# UCC27511_MSFTDRIVER.net
KiCad netlist of a schematic drawn in Altium Designer
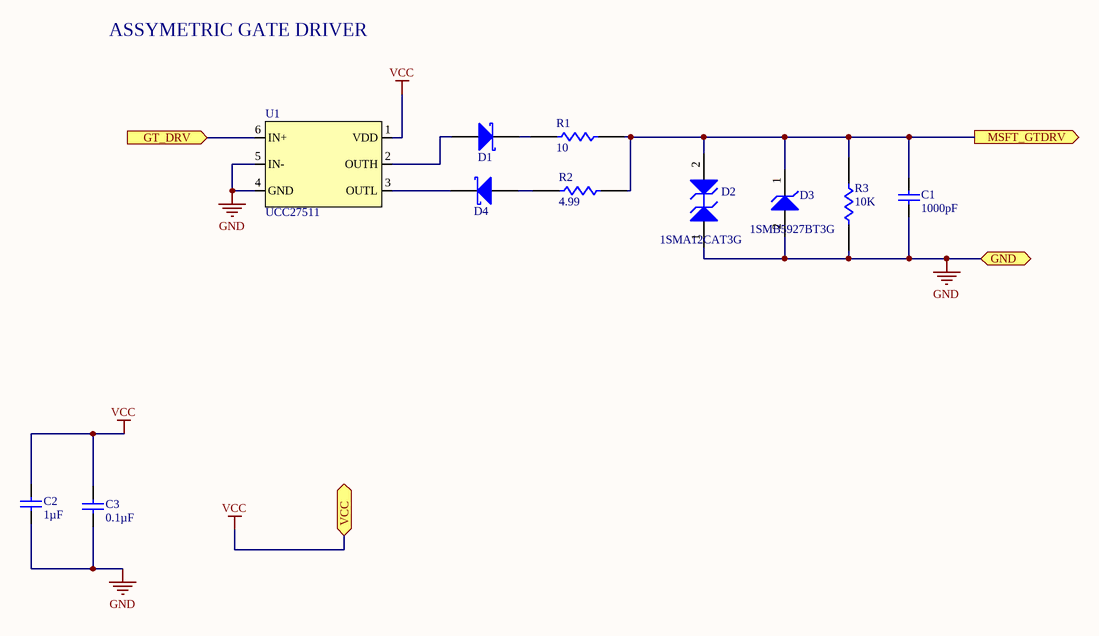
[diagram p0: UCC27511_MSFTDRIVER.SchDoc]

(export (version "E")
  (design (tool "Eeschema 10.0.6"))
  (components
    (comp (ref "C1")
      (value "C0805C102J5GACTU")
      (footprint "CAP0805_NEW")
      (description "CAP CER 1000PF 50V C0G/NP0 0805")
      (fields
        (field (name "MANUFACTURER") "KEMET")
        (field (name "TOLERANCE") "±5%")
        (field (name "CAPACITANCE") "1000pF")
      )
      (libsource (lib "ucc28180-V04") (part "C0805C102J5GACTU"))
    )
    (comp (ref "C2")
      (value "CC0805JKX7R9BB105")
      (footprint "CAP0805_NEW")
      (description "CAP CER 1UF 50V X7R 0805")
      (fields
        (field (name "MANUFACTURER") "Yageo")
        (field (name "TOLERANCE") "±5%")
        (field (name "CAPACITANCE") "1µF")
      )
      (libsource (lib "ucc28180-V04") (part "CC0805JKX7R9BB105"))
    )
    (comp (ref "C3")
      (value "C0805C104J5RACAUTO")
      (footprint "CAP0805_NEW")
      (description "CAP CER 0.1UF 50V X7R 0805")
      (fields
        (field (name "MANUFACTURER") "KEMET")
        (field (name "TOLERANCE") "±5%")
        (field (name "CAPACITANCE") "0.1µF")
      )
      (libsource (lib "ucc28180-V04") (part "C0805C104J5RACAUTO"))
    )
    (comp (ref "D1")
      (value "DB2W40300L")
      (footprint "Mini2-F3-B")
      (fields (field (name "MANUFACTURER") "Panasonic"))
      (libsource (lib "ucc28180") (part "DB2W40300L"))
    )
    (comp (ref "D2")
      (value "1SMA12CAT3G")
      (footprint "ONSC-SMA-2-403D-02_F_V")
      (description "400 W Peak Power Zener Transient Voltage Suppressor, 2-Pin SMA, Pb-Free, Tape and Reel")
      (fields (field (name "MANUFACTURER") "On Semiconductor"))
      (libsource (lib "ON Semi Transient Voltage Suppressors (TVS)") (part "1SMA12CAT3G"))
    )
    (comp (ref "D3")
      (value "1SMB5927BT3G")
      (footprint "ONSC-SMB-2-403A-03_H_V")
      (description "3 W Zener Voltage Regulator, 2-Pin SMB, Pb-Free, Tape and Reel")
      (fields (field (name "MANUFACTURER") "On Semiconductor"))
      (libsource (lib "ON Semi Zener Diodes") (part "1SMB5927BT3G"))
    )
    (comp (ref "D4")
      (value "DB2W40300L")
      (footprint "Mini2-F3-B")
      (fields (field (name "MANUFACTURER") "Panasonic"))
      (libsource (lib "ucc28180") (part "DB2W40300L"))
    )
    (comp (ref "R1")
      (value "CRCW0805R10")
      (footprint "RES0805")
      (fields (field (name "RESISTANCE") "10"))
      (libsource (lib "ucc28180") (part "CRCW0805R10"))
    )
    (comp (ref "R2")
      (value "CRCW0805R4.99")
      (footprint "RES0805")
      (fields (field (name "RESISTANCE") "4.99"))
      (libsource (lib "ucc28180") (part "CRCW0805R4.99"))
    )
    (comp (ref "R3")
      (value "TNPW080510K0FEEA")
      (footprint "RES0805_New")
      (description "RES 10K OHM 1% 1/5W 0805")
      (fields
        (field (name "MANUFACTURER") "Vishay Dale")
        (field (name "TOLERANCE") "±1%")
        (field (name "RESISTANCE") "10K")
      )
      (libsource (lib "ucc28180-V04") (part "TNPW080510K0FEEA"))
    )
    (comp (ref "U1")
      (value "UCC27511DBV")
      (footprint "SOP6")
      (fields (field (name "IC NAME") "UCC27511"))
      (libsource (lib "ucc28180") (part "UCC27511DBV"))
    )
  )
  (nets
    (net (code "1") (name "/GT_DRV") (class "Default")
      (node (ref "U1") (pin "6") (pinfunction "IN+_6") (pintype "input"))
    )
    (net (code "2") (name "/MSFT_GTDRV") (class "Default")
      (node (ref "C1") (pin "2") (pinfunction "2_2") (pintype "passive"))
      (node (ref "D2") (pin "2") (pinfunction "A2_2") (pintype "passive"))
      (node (ref "D3") (pin "1") (pinfunction "K_1") (pintype "passive"))
      (node (ref "R1") (pin "1") (pinfunction "1_1") (pintype "passive"))
      (node (ref "R2") (pin "1") (pinfunction "1_1") (pintype "passive"))
      (node (ref "R3") (pin "1") (pinfunction "1_1") (pintype "passive"))
    )
    (net (code "3") (name "GND") (class "Default")
      (node (ref "C1") (pin "1") (pinfunction "1_1") (pintype "passive"))
      (node (ref "C2") (pin "1") (pinfunction "1_1") (pintype "passive"))
      (node (ref "C3") (pin "1") (pinfunction "1_1") (pintype "passive"))
      (node (ref "D2") (pin "1") (pinfunction "A1_1") (pintype "passive"))
      (node (ref "D3") (pin "2") (pinfunction "A_2") (pintype "passive"))
      (node (ref "R3") (pin "2") (pinfunction "2_2") (pintype "passive"))
      (node (ref "U1") (pin "4") (pinfunction "GND_4") (pintype "passive"))
      (node (ref "U1") (pin "5") (pinfunction "IN-_5") (pintype "input"))
    )
    (net (code "4") (name "Net-(D1-A)") (class "Default")
      (node (ref "D1") (pin "3") (pinfunction "A_3") (pintype "passive"))
      (node (ref "U1") (pin "2") (pinfunction "OUTH_2") (pintype "output"))
    )
    (net (code "5") (name "Net-(D1-K)") (class "Default")
      (node (ref "D1") (pin "1") (pinfunction "K_1") (pintype "passive"))
      (node (ref "R1") (pin "2") (pinfunction "2_2") (pintype "passive"))
    )
    (net (code "6") (name "Net-(D4-A)") (class "Default")
      (node (ref "D4") (pin "3") (pinfunction "A_3") (pintype "passive"))
      (node (ref "R2") (pin "2") (pinfunction "2_2") (pintype "passive"))
    )
    (net (code "7") (name "Net-(D4-K)") (class "Default")
      (node (ref "D4") (pin "1") (pinfunction "K_1") (pintype "passive"))
      (node (ref "U1") (pin "3") (pinfunction "OUTL_3") (pintype "output"))
    )
    (net (code "8") (name "VCC") (class "Default")
      (node (ref "C2") (pin "2") (pinfunction "2_2") (pintype "passive"))
      (node (ref "C3") (pin "2") (pinfunction "2_2") (pintype "passive"))
      (node (ref "U1") (pin "1") (pinfunction "VDD_1") (pintype "passive"))
    )
  )
)
